# Button.net
KiCad netlist of a schematic drawn in Altium Designer
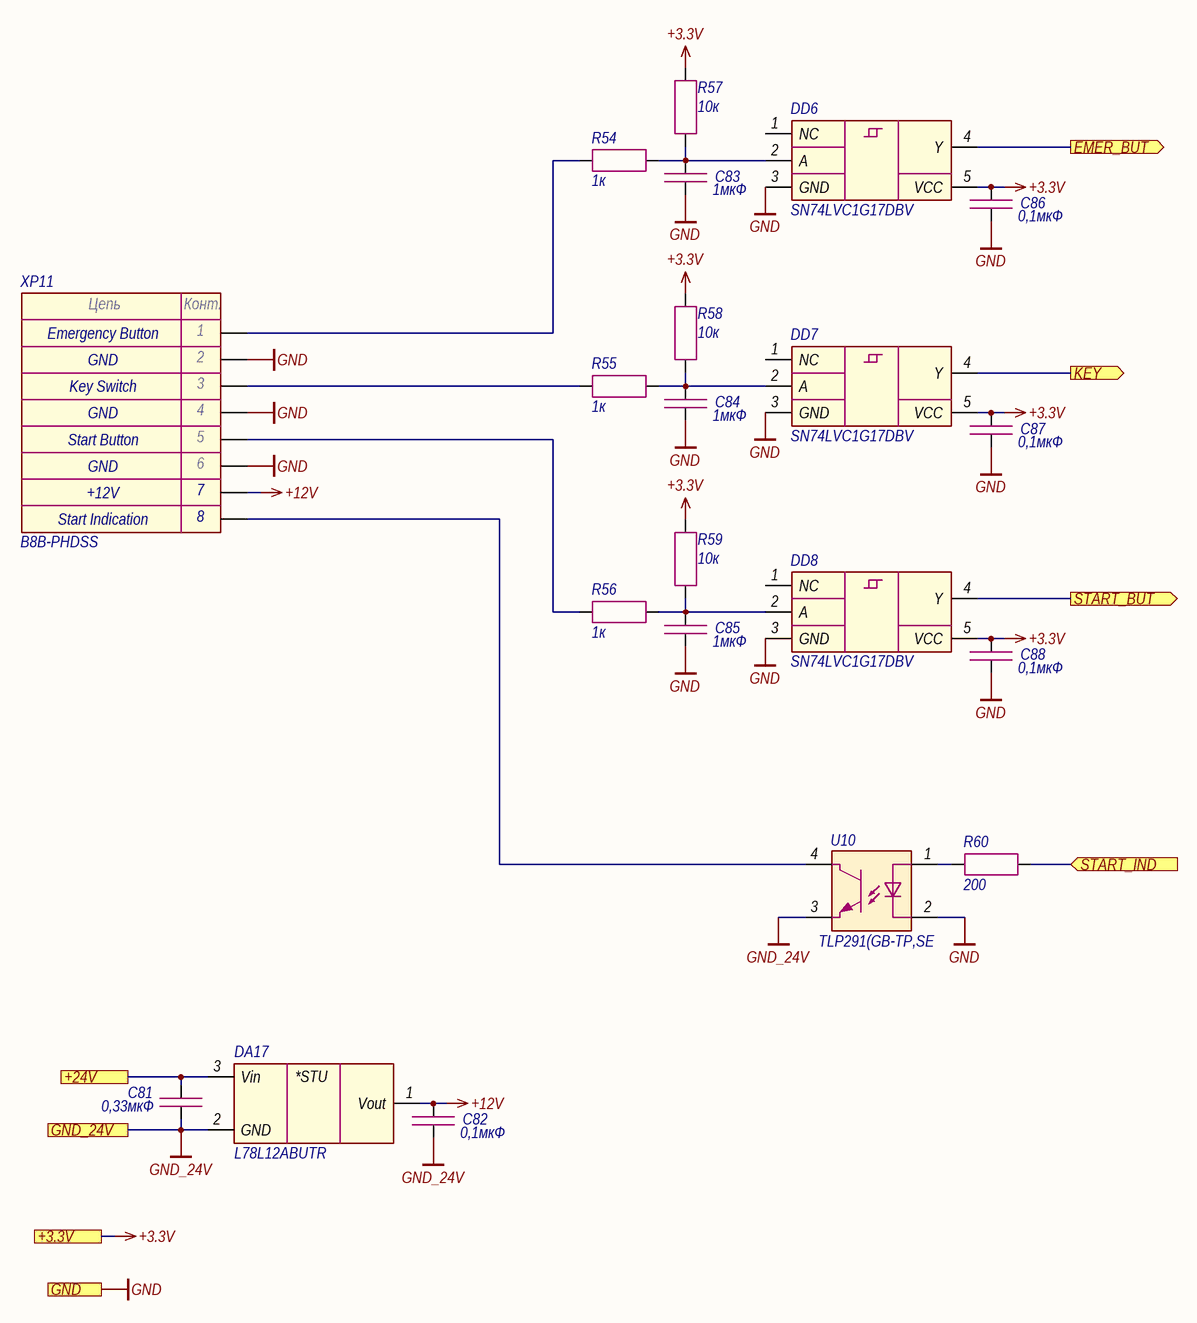
[diagram p0: Button.SchDoc]

(export (version "E")
  (design (tool "Eeschema 10.0.6"))
  (components
    (comp (ref "C81")
      (value "0,33мкФ")
      (footprint "Pcb_library:CAP_0805")
      (fields (field (name "MANUFACTURER") "Murata"))
      (libsource (lib "Schem_library") (part "Capacitor"))
    )
    (comp (ref "C82")
      (value "0,1мкФ")
      (footprint "Pcb_library:CAP_0603")
      (fields (field (name "MANUFACTURER") "Murata"))
      (libsource (lib "Schem_library") (part "Capacitor"))
    )
    (comp (ref "C83")
      (value "1мкФ")
      (footprint "Pcb_library:CAP_0603")
      (fields (field (name "MANUFACTURER") "Murata"))
      (libsource (lib "Schem_library") (part "Capacitor"))
    )
    (comp (ref "C84")
      (value "1мкФ")
      (footprint "Pcb_library:CAP_0603")
      (fields (field (name "MANUFACTURER") "Murata"))
      (libsource (lib "Schem_library") (part "Capacitor"))
    )
    (comp (ref "C85")
      (value "1мкФ")
      (footprint "Pcb_library:CAP_0603")
      (fields (field (name "MANUFACTURER") "Murata"))
      (libsource (lib "Schem_library") (part "Capacitor"))
    )
    (comp (ref "C86")
      (value "0,1мкФ")
      (footprint "Pcb_library:CAP_0603")
      (fields (field (name "MANUFACTURER") "Murata"))
      (libsource (lib "Schem_library") (part "Capacitor"))
    )
    (comp (ref "C87")
      (value "0,1мкФ")
      (footprint "Pcb_library:CAP_0603")
      (fields (field (name "MANUFACTURER") "Murata"))
      (libsource (lib "Schem_library") (part "Capacitor"))
    )
    (comp (ref "C88")
      (value "0,1мкФ")
      (footprint "Pcb_library:CAP_0603")
      (fields (field (name "MANUFACTURER") "Murata"))
      (libsource (lib "Schem_library") (part "Capacitor"))
    )
    (comp (ref "DA17")
      (value "L78L12ABUTR")
      (footprint "Pcb_library:SOT-89")
      (fields (field (name "MANUFACTURER") "STMicroelectronics"))
      (libsource (lib "Schem_library") (part "LD2981ABU50TR"))
    )
    (comp (ref "DD6")
      (value "SN74LVC1G17DBV")
      (footprint "Pcb_library:SOT-23-5")
      (fields (field (name "MANUFACTURER") "Texas Instruments"))
      (libsource (lib "Schem_library") (part "SN74LVC1G17"))
    )
    (comp (ref "DD7")
      (value "SN74LVC1G17DBV")
      (footprint "Pcb_library:SOT-23-5")
      (fields (field (name "MANUFACTURER") "Texas Instruments"))
      (libsource (lib "Schem_library") (part "SN74LVC1G17"))
    )
    (comp (ref "DD8")
      (value "SN74LVC1G17DBV")
      (footprint "Pcb_library:SOT-23-5")
      (fields (field (name "MANUFACTURER") "Texas Instruments"))
      (libsource (lib "Schem_library") (part "SN74LVC1G17"))
    )
    (comp (ref "R54")
      (value "1к")
      (footprint "Pcb_library:RES_0603")
      (fields (field (name "MANUFACTURER") "Yageo"))
      (libsource (lib "Schem_library") (part "Resistor"))
    )
    (comp (ref "R55")
      (value "1к")
      (footprint "Pcb_library:RES_0603")
      (fields (field (name "MANUFACTURER") "Yageo"))
      (libsource (lib "Schem_library") (part "Resistor"))
    )
    (comp (ref "R56")
      (value "1к")
      (footprint "Pcb_library:RES_0603")
      (fields (field (name "MANUFACTURER") "Yageo"))
      (libsource (lib "Schem_library") (part "Resistor"))
    )
    (comp (ref "R57")
      (value "10к")
      (footprint "Pcb_library:RES_0603")
      (fields (field (name "MANUFACTURER") "Yageo"))
      (libsource (lib "Schem_library") (part "Resistor"))
    )
    (comp (ref "R58")
      (value "10к")
      (footprint "Pcb_library:RES_0603")
      (fields (field (name "MANUFACTURER") "Yageo"))
      (libsource (lib "Schem_library") (part "Resistor"))
    )
    (comp (ref "R59")
      (value "10к")
      (footprint "Pcb_library:RES_0603")
      (fields (field (name "MANUFACTURER") "Yageo"))
      (libsource (lib "Schem_library") (part "Resistor"))
    )
    (comp (ref "R60")
      (value "200")
      (footprint "Pcb_library:RES_0603")
      (fields (field (name "MANUFACTURER") "Yageo"))
      (libsource (lib "Schem_library") (part "Resistor"))
    )
    (comp (ref "U10")
      (value "TLP291(GB-TP,SE")
      (footprint "Pcb_library:11-3C1")
      (fields (field (name "MANUFACTURER") "Toshiba"))
      (libsource (lib "Schem_library") (part "TLP291"))
    )
    (comp (ref "XP11")
      (value "B8B-PHDSS")
      (footprint "Pcb_library:B8B-PHDSS")
      (fields (field (name "MANUFACTURER") "JST"))
      (libsource (lib "Schem_library") (part "Connector-8"))
    )
  )
  (nets
    (net (code "1") (name "+3.3V") (class "Default")
      (node (ref "C86") (pin "1") (pinfunction "1_1") (pintype "passive"))
      (node (ref "C87") (pin "1") (pinfunction "1_1") (pintype "passive"))
      (node (ref "C88") (pin "1") (pinfunction "1_1") (pintype "passive"))
      (node (ref "DD6") (pin "5") (pinfunction "VCC_5") (pintype "passive"))
      (node (ref "DD7") (pin "5") (pinfunction "VCC_5") (pintype "passive"))
      (node (ref "DD8") (pin "5") (pinfunction "VCC_5") (pintype "passive"))
      (node (ref "R57") (pin "2") (pinfunction "2_2") (pintype "passive"))
      (node (ref "R58") (pin "2") (pinfunction "2_2") (pintype "passive"))
      (node (ref "R59") (pin "2") (pinfunction "2_2") (pintype "passive"))
    )
    (net (code "2") (name "+12V") (class "Default")
      (node (ref "C82") (pin "1") (pinfunction "1_1") (pintype "passive"))
      (node (ref "DA17") (pin "1") (pinfunction "Vout_1") (pintype "passive"))
      (node (ref "XP11") (pin "7") (pintype "passive"))
    )
    (net (code "3") (name "/+24V") (class "Default")
      (node (ref "C81") (pin "2") (pinfunction "2_2") (pintype "passive"))
      (node (ref "DA17") (pin "3") (pinfunction "Vin_3") (pintype "passive"))
    )
    (net (code "4") (name "/EMER_BUT") (class "Default")
      (node (ref "DD6") (pin "4") (pinfunction "Y_4") (pintype "passive"))
    )
    (net (code "5") (name "/KEY") (class "Default")
      (node (ref "DD7") (pin "4") (pinfunction "Y_4") (pintype "passive"))
    )
    (net (code "6") (name "/START_BUT") (class "Default")
      (node (ref "DD8") (pin "4") (pinfunction "Y_4") (pintype "passive"))
    )
    (net (code "7") (name "/START_IND") (class "Default")
      (node (ref "R60") (pin "2") (pinfunction "2_2") (pintype "passive"))
    )
    (net (code "8") (name "GND") (class "Default")
      (node (ref "C83") (pin "2") (pinfunction "2_2") (pintype "passive"))
      (node (ref "C84") (pin "2") (pinfunction "2_2") (pintype "passive"))
      (node (ref "C85") (pin "2") (pinfunction "2_2") (pintype "passive"))
      (node (ref "C86") (pin "2") (pinfunction "2_2") (pintype "passive"))
      (node (ref "C87") (pin "2") (pinfunction "2_2") (pintype "passive"))
      (node (ref "C88") (pin "2") (pinfunction "2_2") (pintype "passive"))
      (node (ref "DD6") (pin "3") (pinfunction "GND_3") (pintype "passive"))
      (node (ref "DD7") (pin "3") (pinfunction "GND_3") (pintype "passive"))
      (node (ref "DD8") (pin "3") (pinfunction "GND_3") (pintype "passive"))
      (node (ref "U10") (pin "2") (pintype "passive"))
      (node (ref "XP11") (pin "2") (pintype "passive"))
      (node (ref "XP11") (pin "4") (pintype "passive"))
      (node (ref "XP11") (pin "6") (pintype "passive"))
    )
    (net (code "9") (name "GND_24V") (class "Default")
      (node (ref "C81") (pin "1") (pinfunction "1_1") (pintype "passive"))
      (node (ref "C82") (pin "2") (pinfunction "2_2") (pintype "passive"))
      (node (ref "DA17") (pin "2") (pinfunction "GND_2") (pintype "passive"))
      (node (ref "U10") (pin "3") (pintype "passive"))
    )
    (net (code "10") (name "Net-(DD6-A)") (class "Default")
      (node (ref "C83") (pin "1") (pinfunction "1_1") (pintype "passive"))
      (node (ref "DD6") (pin "2") (pinfunction "A_2") (pintype "passive"))
      (node (ref "R54") (pin "2") (pinfunction "2_2") (pintype "passive"))
      (node (ref "R57") (pin "1") (pinfunction "1_1") (pintype "passive"))
    )
    (net (code "11") (name "Net-(DD7-A)") (class "Default")
      (node (ref "C84") (pin "1") (pinfunction "1_1") (pintype "passive"))
      (node (ref "DD7") (pin "2") (pinfunction "A_2") (pintype "passive"))
      (node (ref "R55") (pin "2") (pinfunction "2_2") (pintype "passive"))
      (node (ref "R58") (pin "1") (pinfunction "1_1") (pintype "passive"))
    )
    (net (code "12") (name "Net-(DD8-A)") (class "Default")
      (node (ref "C85") (pin "1") (pinfunction "1_1") (pintype "passive"))
      (node (ref "DD8") (pin "2") (pinfunction "A_2") (pintype "passive"))
      (node (ref "R56") (pin "2") (pinfunction "2_2") (pintype "passive"))
      (node (ref "R59") (pin "1") (pinfunction "1_1") (pintype "passive"))
    )
    (net (code "13") (name "Net-(R54-Pad1)") (class "Default")
      (node (ref "R54") (pin "1") (pinfunction "1_1") (pintype "passive"))
      (node (ref "XP11") (pin "1") (pintype "passive"))
    )
    (net (code "14") (name "Net-(R55-Pad1)") (class "Default")
      (node (ref "R55") (pin "1") (pinfunction "1_1") (pintype "passive"))
      (node (ref "XP11") (pin "3") (pintype "passive"))
    )
    (net (code "15") (name "Net-(R56-Pad1)") (class "Default")
      (node (ref "R56") (pin "1") (pinfunction "1_1") (pintype "passive"))
      (node (ref "XP11") (pin "5") (pintype "passive"))
    )
    (net (code "16") (name "Net-(R60-Pad1)") (class "Default")
      (node (ref "R60") (pin "1") (pinfunction "1_1") (pintype "passive"))
      (node (ref "U10") (pin "1") (pintype "passive"))
    )
    (net (code "17") (name "Net-(U10-Pad4)") (class "Default")
      (node (ref "U10") (pin "4") (pintype "passive"))
      (node (ref "XP11") (pin "8") (pintype "passive"))
    )
    (net (code "18") (name "unconnected-(DD6-NC-Pad1)") (class "Default")
      (node (ref "DD6") (pin "1") (pinfunction "NC_1") (pintype "passive"))
    )
    (net (code "19") (name "unconnected-(DD7-NC-Pad1)") (class "Default")
      (node (ref "DD7") (pin "1") (pinfunction "NC_1") (pintype "passive"))
    )
    (net (code "20") (name "unconnected-(DD8-NC-Pad1)") (class "Default")
      (node (ref "DD8") (pin "1") (pinfunction "NC_1") (pintype "passive"))
    )
  )
)
